# 10_DDR3_RAM.net
KiCad netlist of a schematic drawn in Altium Designer
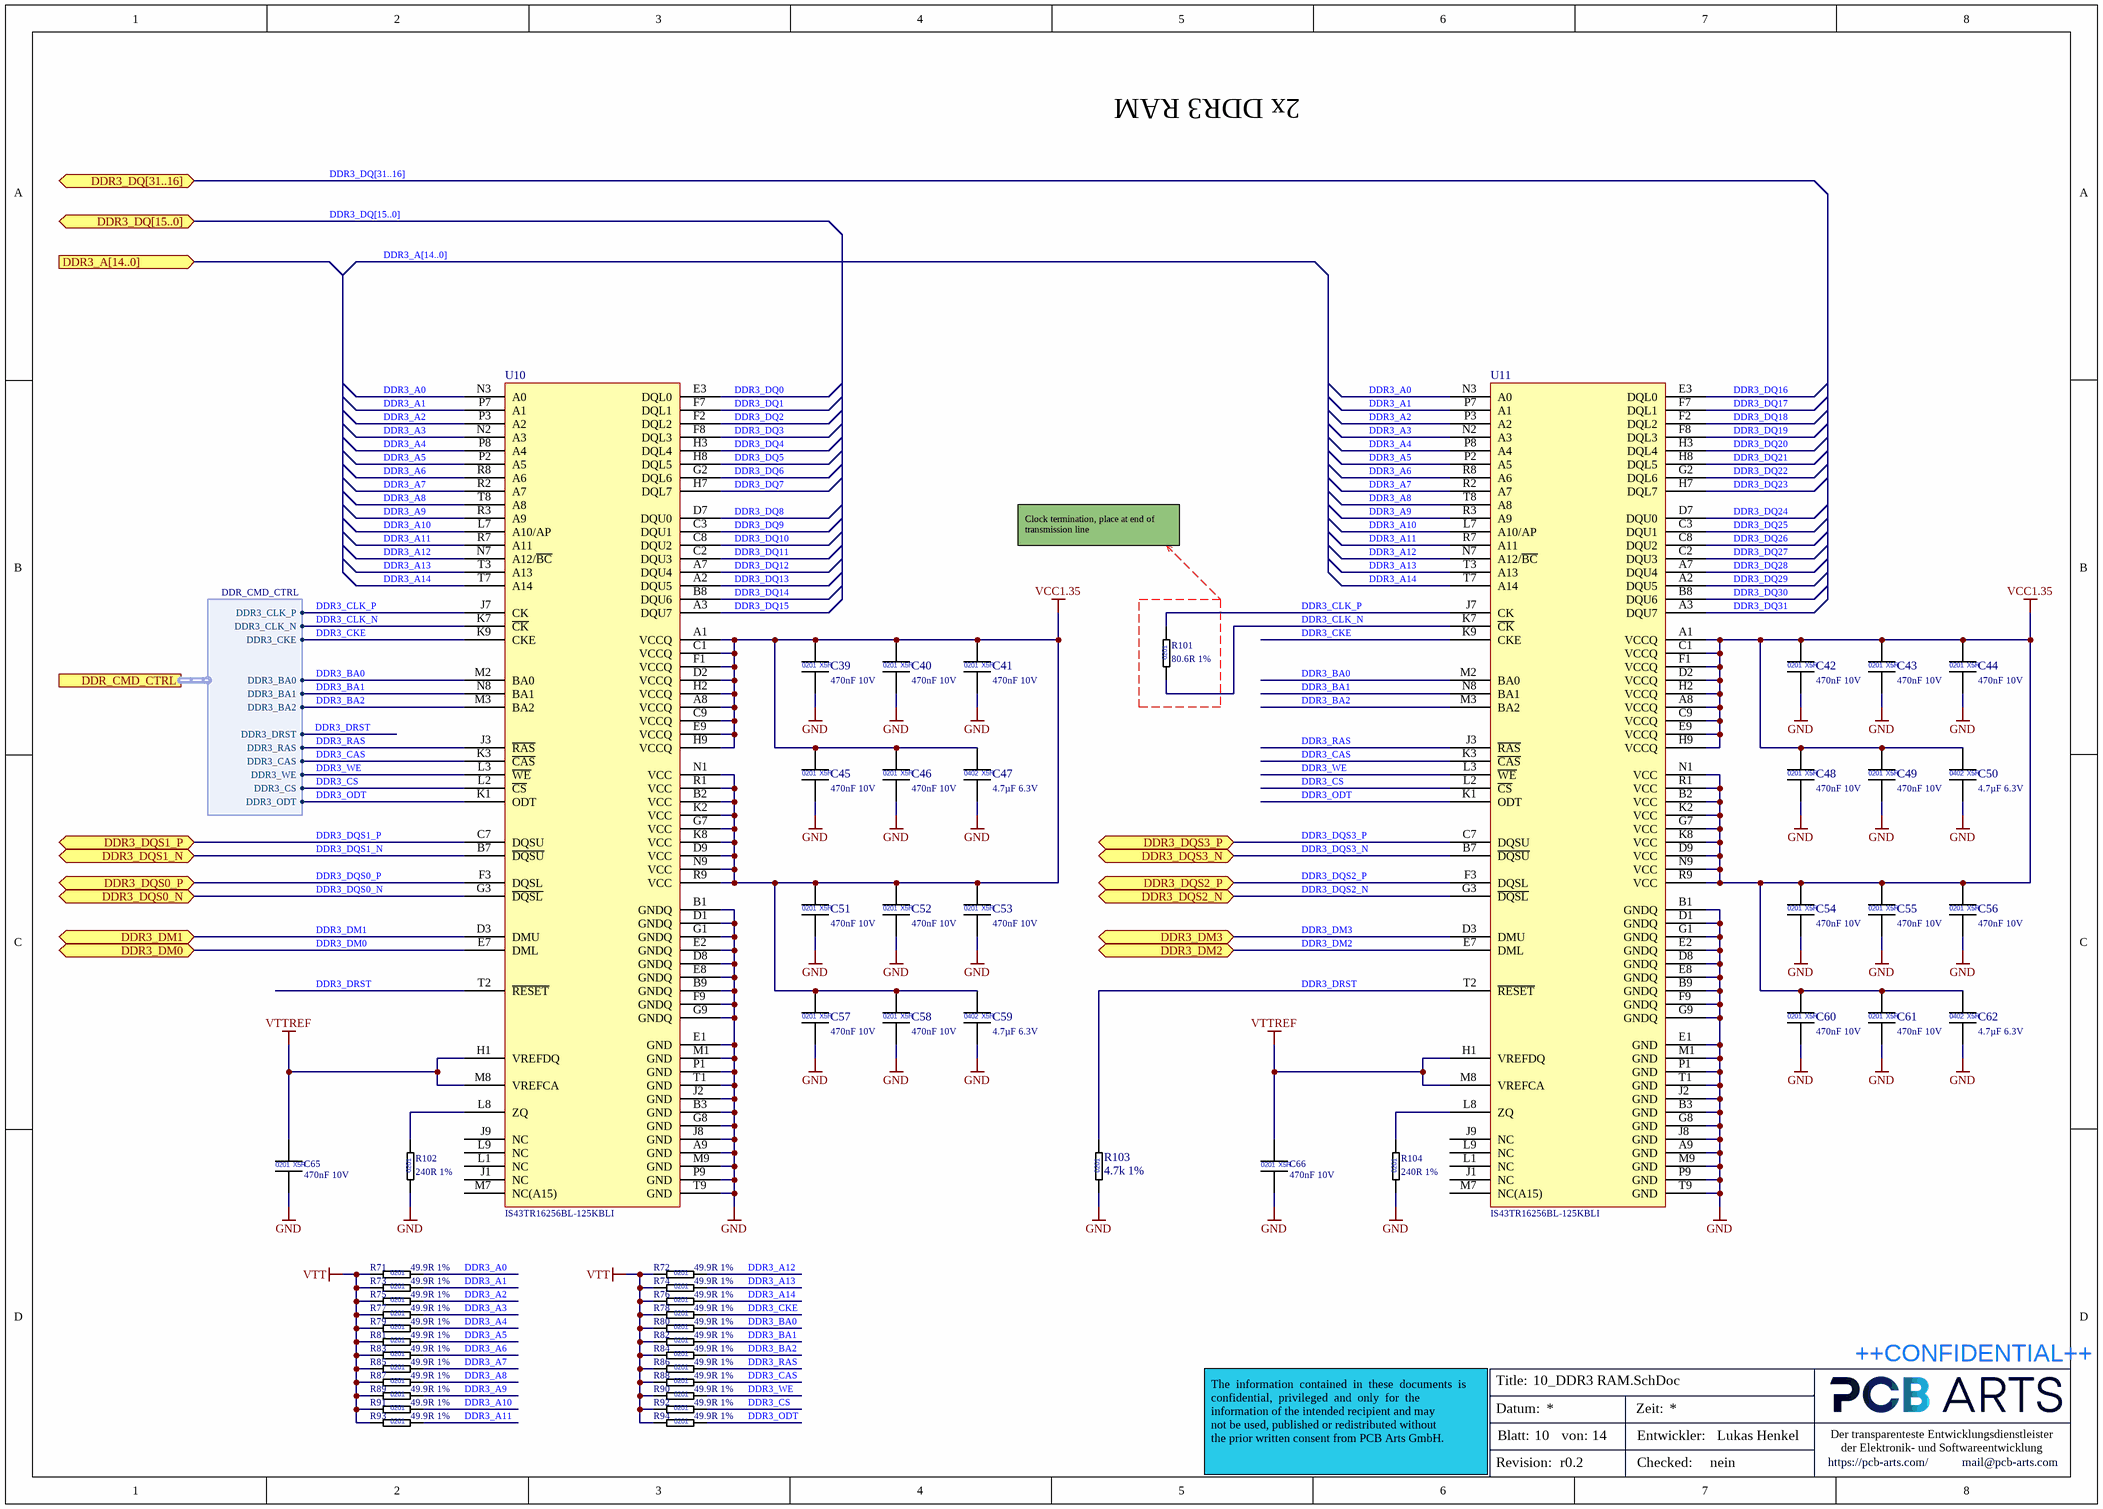
[diagram p0: 10_DDR3 RAM.SchDoc]

(export (version "E")
  (design (tool "Eeschema 10.0.6"))
  (components
    (comp (ref "C39")
      (value "470nF 10V")
      (footprint "Zynq-Feather-HD:CAPC0603X03L")
      (description "Multilayer Ceramic Capacitors MLCC - SMD/SMT 0201 10VDC")
      (libsource (lib "Zynq-Feather-HD") (part "CAP_0201_470nF_10V"))
    )
    (comp (ref "C40")
      (value "470nF 10V")
      (footprint "Zynq-Feather-HD:CAPC0603X03L")
      (description "Multilayer Ceramic Capacitors MLCC - SMD/SMT 0201 10VDC")
      (libsource (lib "Zynq-Feather-HD") (part "CAP_0201_470nF_10V"))
    )
    (comp (ref "C41")
      (value "470nF 10V")
      (footprint "Zynq-Feather-HD:CAPC0603X03L")
      (description "Multilayer Ceramic Capacitors MLCC - SMD/SMT 0201 10VDC")
      (libsource (lib "Zynq-Feather-HD") (part "CAP_0201_470nF_10V"))
    )
    (comp (ref "C42")
      (value "470nF 10V")
      (footprint "Zynq-Feather-HD:CAPC0603X03L")
      (description "Multilayer Ceramic Capacitors MLCC - SMD/SMT 0201 10VDC")
      (libsource (lib "Zynq-Feather-HD") (part "CAP_0201_470nF_10V"))
    )
    (comp (ref "C43")
      (value "470nF 10V")
      (footprint "Zynq-Feather-HD:CAPC0603X03L")
      (description "Multilayer Ceramic Capacitors MLCC - SMD/SMT 0201 10VDC")
      (libsource (lib "Zynq-Feather-HD") (part "CAP_0201_470nF_10V"))
    )
    (comp (ref "C44")
      (value "470nF 10V")
      (footprint "Zynq-Feather-HD:CAPC0603X03L")
      (description "Multilayer Ceramic Capacitors MLCC - SMD/SMT 0201 10VDC")
      (libsource (lib "Zynq-Feather-HD") (part "CAP_0201_470nF_10V"))
    )
    (comp (ref "C45")
      (value "470nF 10V")
      (footprint "Zynq-Feather-HD:CAPC0603X03L")
      (description "Multilayer Ceramic Capacitors MLCC - SMD/SMT 0201 10VDC")
      (libsource (lib "Zynq-Feather-HD") (part "CAP_0201_470nF_10V"))
    )
    (comp (ref "C46")
      (value "470nF 10V")
      (footprint "Zynq-Feather-HD:CAPC0603X03L")
      (description "Multilayer Ceramic Capacitors MLCC - SMD/SMT 0201 10VDC")
      (libsource (lib "Zynq-Feather-HD") (part "CAP_0201_470nF_10V"))
    )
    (comp (ref "C47")
      (value "4.7µF 6.3V")
      (footprint "Zynq-Feather-HD:CAPC1005X06L")
      (description "Multilayer Ceramic Capacitors MLCC - SMD/SMT 0402 6.3VDC")
      (libsource (lib "Zynq-Feather-HD") (part "CAP_0402_4.7µ_6.3V"))
    )
    (comp (ref "C48")
      (value "470nF 10V")
      (footprint "Zynq-Feather-HD:CAPC0603X03L")
      (description "Multilayer Ceramic Capacitors MLCC - SMD/SMT 0201 10VDC")
      (libsource (lib "Zynq-Feather-HD") (part "CAP_0201_470nF_10V"))
    )
    (comp (ref "C49")
      (value "470nF 10V")
      (footprint "Zynq-Feather-HD:CAPC0603X03L")
      (description "Multilayer Ceramic Capacitors MLCC - SMD/SMT 0201 10VDC")
      (libsource (lib "Zynq-Feather-HD") (part "CAP_0201_470nF_10V"))
    )
    (comp (ref "C50")
      (value "4.7µF 6.3V")
      (footprint "Zynq-Feather-HD:CAPC1005X06L")
      (description "Multilayer Ceramic Capacitors MLCC - SMD/SMT 0402 6.3VDC")
      (libsource (lib "Zynq-Feather-HD") (part "CAP_0402_4.7µ_6.3V"))
    )
    (comp (ref "C51")
      (value "470nF 10V")
      (footprint "Zynq-Feather-HD:CAPC0603X03L")
      (description "Multilayer Ceramic Capacitors MLCC - SMD/SMT 0201 10VDC")
      (libsource (lib "Zynq-Feather-HD") (part "CAP_0201_470nF_10V"))
    )
    (comp (ref "C52")
      (value "470nF 10V")
      (footprint "Zynq-Feather-HD:CAPC0603X03L")
      (description "Multilayer Ceramic Capacitors MLCC - SMD/SMT 0201 10VDC")
      (libsource (lib "Zynq-Feather-HD") (part "CAP_0201_470nF_10V"))
    )
    (comp (ref "C53")
      (value "470nF 10V")
      (footprint "Zynq-Feather-HD:CAPC0603X03L")
      (description "Multilayer Ceramic Capacitors MLCC - SMD/SMT 0201 10VDC")
      (libsource (lib "Zynq-Feather-HD") (part "CAP_0201_470nF_10V"))
    )
    (comp (ref "C54")
      (value "470nF 10V")
      (footprint "Zynq-Feather-HD:CAPC0603X03L")
      (description "Multilayer Ceramic Capacitors MLCC - SMD/SMT 0201 10VDC")
      (libsource (lib "Zynq-Feather-HD") (part "CAP_0201_470nF_10V"))
    )
    (comp (ref "C55")
      (value "470nF 10V")
      (footprint "Zynq-Feather-HD:CAPC0603X03L")
      (description "Multilayer Ceramic Capacitors MLCC - SMD/SMT 0201 10VDC")
      (libsource (lib "Zynq-Feather-HD") (part "CAP_0201_470nF_10V"))
    )
    (comp (ref "C56")
      (value "470nF 10V")
      (footprint "Zynq-Feather-HD:CAPC0603X03L")
      (description "Multilayer Ceramic Capacitors MLCC - SMD/SMT 0201 10VDC")
      (libsource (lib "Zynq-Feather-HD") (part "CAP_0201_470nF_10V"))
    )
    (comp (ref "C57")
      (value "470nF 10V")
      (footprint "Zynq-Feather-HD:CAPC0603X03L")
      (description "Multilayer Ceramic Capacitors MLCC - SMD/SMT 0201 10VDC")
      (libsource (lib "Zynq-Feather-HD") (part "CAP_0201_470nF_10V"))
    )
    (comp (ref "C58")
      (value "470nF 10V")
      (footprint "Zynq-Feather-HD:CAPC0603X03L")
      (description "Multilayer Ceramic Capacitors MLCC - SMD/SMT 0201 10VDC")
      (libsource (lib "Zynq-Feather-HD") (part "CAP_0201_470nF_10V"))
    )
    (comp (ref "C59")
      (value "4.7µF 6.3V")
      (footprint "Zynq-Feather-HD:CAPC1005X06L")
      (description "Multilayer Ceramic Capacitors MLCC - SMD/SMT 0402 6.3VDC")
      (libsource (lib "Zynq-Feather-HD") (part "CAP_0402_4.7µ_6.3V"))
    )
    (comp (ref "C60")
      (value "470nF 10V")
      (footprint "Zynq-Feather-HD:CAPC0603X03L")
      (description "Multilayer Ceramic Capacitors MLCC - SMD/SMT 0201 10VDC")
      (libsource (lib "Zynq-Feather-HD") (part "CAP_0201_470nF_10V"))
    )
    (comp (ref "C61")
      (value "470nF 10V")
      (footprint "Zynq-Feather-HD:CAPC0603X03L")
      (description "Multilayer Ceramic Capacitors MLCC - SMD/SMT 0201 10VDC")
      (libsource (lib "Zynq-Feather-HD") (part "CAP_0201_470nF_10V"))
    )
    (comp (ref "C62")
      (value "4.7µF 6.3V")
      (footprint "Zynq-Feather-HD:CAPC1005X06L")
      (description "Multilayer Ceramic Capacitors MLCC - SMD/SMT 0402 6.3VDC")
      (libsource (lib "Zynq-Feather-HD") (part "CAP_0402_4.7µ_6.3V"))
    )
    (comp (ref "C65")
      (value "470nF 10V")
      (footprint "Zynq-Feather-HD:CAPC0603X03L")
      (description "Multilayer Ceramic Capacitors MLCC - SMD/SMT 0201 10VDC")
      (libsource (lib "Zynq-Feather-HD") (part "CAP_0201_470nF_10V"))
    )
    (comp (ref "C66")
      (value "470nF 10V")
      (footprint "Zynq-Feather-HD:CAPC0603X03L")
      (description "Multilayer Ceramic Capacitors MLCC - SMD/SMT 0201 10VDC")
      (libsource (lib "Zynq-Feather-HD") (part "CAP_0201_470nF_10V"))
    )
    (comp (ref "R71")
      (value "49.9R 1%")
      (footprint "Zynq-Feather-HD:RESC0603X03L")
      (description "Thick Film Resistors - SMD 49.9R OHM 1%")
      (libsource (lib "Zynq-Feather-HD") (part "RES_0201_49.9R_1%"))
    )
    (comp (ref "R72")
      (value "49.9R 1%")
      (footprint "Zynq-Feather-HD:RESC0603X03L")
      (description "Thick Film Resistors - SMD 49.9R OHM 1%")
      (libsource (lib "Zynq-Feather-HD") (part "RES_0201_49.9R_1%"))
    )
    (comp (ref "R73")
      (value "49.9R 1%")
      (footprint "Zynq-Feather-HD:RESC0603X03L")
      (description "Thick Film Resistors - SMD 49.9R OHM 1%")
      (libsource (lib "Zynq-Feather-HD") (part "RES_0201_49.9R_1%"))
    )
    (comp (ref "R74")
      (value "49.9R 1%")
      (footprint "Zynq-Feather-HD:RESC0603X03L")
      (description "Thick Film Resistors - SMD 49.9R OHM 1%")
      (libsource (lib "Zynq-Feather-HD") (part "RES_0201_49.9R_1%"))
    )
    (comp (ref "R75")
      (value "49.9R 1%")
      (footprint "Zynq-Feather-HD:RESC0603X03L")
      (description "Thick Film Resistors - SMD 49.9R OHM 1%")
      (libsource (lib "Zynq-Feather-HD") (part "RES_0201_49.9R_1%"))
    )
    (comp (ref "R76")
      (value "49.9R 1%")
      (footprint "Zynq-Feather-HD:RESC0603X03L")
      (description "Thick Film Resistors - SMD 49.9R OHM 1%")
      (libsource (lib "Zynq-Feather-HD") (part "RES_0201_49.9R_1%"))
    )
    (comp (ref "R77")
      (value "49.9R 1%")
      (footprint "Zynq-Feather-HD:RESC0603X03L")
      (description "Thick Film Resistors - SMD 49.9R OHM 1%")
      (libsource (lib "Zynq-Feather-HD") (part "RES_0201_49.9R_1%"))
    )
    (comp (ref "R78")
      (value "49.9R 1%")
      (footprint "Zynq-Feather-HD:RESC0603X03L")
      (description "Thick Film Resistors - SMD 49.9R OHM 1%")
      (libsource (lib "Zynq-Feather-HD") (part "RES_0201_49.9R_1%"))
    )
    (comp (ref "R79")
      (value "49.9R 1%")
      (footprint "Zynq-Feather-HD:RESC0603X03L")
      (description "Thick Film Resistors - SMD 49.9R OHM 1%")
      (libsource (lib "Zynq-Feather-HD") (part "RES_0201_49.9R_1%"))
    )
    (comp (ref "R80")
      (value "49.9R 1%")
      (footprint "Zynq-Feather-HD:RESC0603X03L")
      (description "Thick Film Resistors - SMD 49.9R OHM 1%")
      (libsource (lib "Zynq-Feather-HD") (part "RES_0201_49.9R_1%"))
    )
    (comp (ref "R81")
      (value "49.9R 1%")
      (footprint "Zynq-Feather-HD:RESC0603X03L")
      (description "Thick Film Resistors - SMD 49.9R OHM 1%")
      (libsource (lib "Zynq-Feather-HD") (part "RES_0201_49.9R_1%"))
    )
    (comp (ref "R82")
      (value "49.9R 1%")
      (footprint "Zynq-Feather-HD:RESC0603X03L")
      (description "Thick Film Resistors - SMD 49.9R OHM 1%")
      (libsource (lib "Zynq-Feather-HD") (part "RES_0201_49.9R_1%"))
    )
    (comp (ref "R83")
      (value "49.9R 1%")
      (footprint "Zynq-Feather-HD:RESC0603X03L")
      (description "Thick Film Resistors - SMD 49.9R OHM 1%")
      (libsource (lib "Zynq-Feather-HD") (part "RES_0201_49.9R_1%"))
    )
    (comp (ref "R84")
      (value "49.9R 1%")
      (footprint "Zynq-Feather-HD:RESC0603X03L")
      (description "Thick Film Resistors - SMD 49.9R OHM 1%")
      (libsource (lib "Zynq-Feather-HD") (part "RES_0201_49.9R_1%"))
    )
    (comp (ref "R85")
      (value "49.9R 1%")
      (footprint "Zynq-Feather-HD:RESC0603X03L")
      (description "Thick Film Resistors - SMD 49.9R OHM 1%")
      (libsource (lib "Zynq-Feather-HD") (part "RES_0201_49.9R_1%"))
    )
    (comp (ref "R86")
      (value "49.9R 1%")
      (footprint "Zynq-Feather-HD:RESC0603X03L")
      (description "Thick Film Resistors - SMD 49.9R OHM 1%")
      (libsource (lib "Zynq-Feather-HD") (part "RES_0201_49.9R_1%"))
    )
    (comp (ref "R87")
      (value "49.9R 1%")
      (footprint "Zynq-Feather-HD:RESC0603X03L")
      (description "Thick Film Resistors - SMD 49.9R OHM 1%")
      (libsource (lib "Zynq-Feather-HD") (part "RES_0201_49.9R_1%"))
    )
    (comp (ref "R88")
      (value "49.9R 1%")
      (footprint "Zynq-Feather-HD:RESC0603X03L")
      (description "Thick Film Resistors - SMD 49.9R OHM 1%")
      (libsource (lib "Zynq-Feather-HD") (part "RES_0201_49.9R_1%"))
    )
    (comp (ref "R89")
      (value "49.9R 1%")
      (footprint "Zynq-Feather-HD:RESC0603X03L")
      (description "Thick Film Resistors - SMD 49.9R OHM 1%")
      (libsource (lib "Zynq-Feather-HD") (part "RES_0201_49.9R_1%"))
    )
    (comp (ref "R90")
      (value "49.9R 1%")
      (footprint "Zynq-Feather-HD:RESC0603X03L")
      (description "Thick Film Resistors - SMD 49.9R OHM 1%")
      (libsource (lib "Zynq-Feather-HD") (part "RES_0201_49.9R_1%"))
    )
    (comp (ref "R91")
      (value "49.9R 1%")
      (footprint "Zynq-Feather-HD:RESC0603X03L")
      (description "Thick Film Resistors - SMD 49.9R OHM 1%")
      (libsource (lib "Zynq-Feather-HD") (part "RES_0201_49.9R_1%"))
    )
    (comp (ref "R92")
      (value "49.9R 1%")
      (footprint "Zynq-Feather-HD:RESC0603X03L")
      (description "Thick Film Resistors - SMD 49.9R OHM 1%")
      (libsource (lib "Zynq-Feather-HD") (part "RES_0201_49.9R_1%"))
    )
    (comp (ref "R93")
      (value "49.9R 1%")
      (footprint "Zynq-Feather-HD:RESC0603X03L")
      (description "Thick Film Resistors - SMD 49.9R OHM 1%")
      (libsource (lib "Zynq-Feather-HD") (part "RES_0201_49.9R_1%"))
    )
    (comp (ref "R94")
      (value "49.9R 1%")
      (footprint "Zynq-Feather-HD:RESC0603X03L")
      (description "Thick Film Resistors - SMD 49.9R OHM 1%")
      (libsource (lib "Zynq-Feather-HD") (part "RES_0201_49.9R_1%"))
    )
    (comp (ref "R101")
      (value "80.6R 1%")
      (footprint "Zynq-Feather-HD:RESC0603X03L")
      (description "Thick Film Resistors - SMD 80.6R OHM 1%")
      (libsource (lib "Zynq-Feather-HD") (part "RES_0201_80.6R_1%"))
    )
    (comp (ref "R102")
      (value "240R 1%")
      (footprint "Zynq-Feather-HD:RESC0603X03L")
      (description "Thick Film Resistors - SMD 240 OHM 1%")
      (libsource (lib "Zynq-Feather-HD") (part "RES_0201_240R_1%"))
    )
    (comp (ref "R103")
      (value "4.7k 1%")
      (footprint "Zynq-Feather-HD:RESC0603X03L")
      (description "Thick Film Resistors - SMD 4.7K OHM 1%")
      (libsource (lib "Zynq-Feather-HD") (part "RES_0201_4.7k_1%"))
    )
    (comp (ref "R104")
      (value "240R 1%")
      (footprint "Zynq-Feather-HD:RESC0603X03L")
      (description "Thick Film Resistors - SMD 240 OHM 1%")
      (libsource (lib "Zynq-Feather-HD") (part "RES_0201_240R_1%"))
    )
    (comp (ref "U10")
      (value "IS43TR16256BL-125KBLI")
      (footprint "Zynq-Feather-HD:BGA96C80P9X16_900X1300X120")
      (description "DRAM 4G, 1.35V, DDR3L, 256Mx16, 1600MT/s @ 11-11-11, 96 ball BGA (9mm x13mm) RoHS, IT")
      (libsource (lib "Zynq-Feather-HD") (part "IS43TR16256BL-125KBLI_DRAM 4G, 1.35V, DDR3L, 256Mx16"))
    )
    (comp (ref "U11")
      (value "IS43TR16256BL-125KBLI")
      (footprint "Zynq-Feather-HD:BGA96C80P9X16_900X1300X120")
      (description "DRAM 4G, 1.35V, DDR3L, 256Mx16, 1600MT/s @ 11-11-11, 96 ball BGA (9mm x13mm) RoHS, IT")
      (libsource (lib "Zynq-Feather-HD") (part "IS43TR16256BL-125KBLI_DRAM 4G, 1.35V, DDR3L, 256Mx16"))
    )
  )
  (nets
    (net (code "2") (name "/DDR3_A0") (class "Default")
      (node (ref "R71") (pin "2") (pinfunction "2_2") (pintype "passive"))
      (node (ref "U10") (pin "N3") (pinfunction "A0_N3") (pintype "passive"))
      (node (ref "U11") (pin "N3") (pinfunction "A0_N3") (pintype "passive"))
    )
    (net (code "3") (name "/DDR3_A1") (class "Default")
      (node (ref "R73") (pin "2") (pinfunction "2_2") (pintype "passive"))
      (node (ref "U10") (pin "P7") (pinfunction "A1_P7") (pintype "passive"))
      (node (ref "U11") (pin "P7") (pinfunction "A1_P7") (pintype "passive"))
    )
    (net (code "4") (name "/DDR3_A2") (class "Default")
      (node (ref "R75") (pin "2") (pinfunction "2_2") (pintype "passive"))
      (node (ref "U10") (pin "P3") (pinfunction "A2_P3") (pintype "passive"))
      (node (ref "U11") (pin "P3") (pinfunction "A2_P3") (pintype "passive"))
    )
    (net (code "5") (name "/DDR3_A3") (class "Default")
      (node (ref "R77") (pin "2") (pinfunction "2_2") (pintype "passive"))
      (node (ref "U10") (pin "N2") (pinfunction "A3_N2") (pintype "passive"))
      (node (ref "U11") (pin "N2") (pinfunction "A3_N2") (pintype "passive"))
    )
    (net (code "6") (name "/DDR3_A4") (class "Default")
      (node (ref "R79") (pin "2") (pinfunction "2_2") (pintype "passive"))
      (node (ref "U10") (pin "P8") (pinfunction "A4_P8") (pintype "passive"))
      (node (ref "U11") (pin "P8") (pinfunction "A4_P8") (pintype "passive"))
    )
    (net (code "7") (name "/DDR3_A5") (class "Default")
      (node (ref "R81") (pin "2") (pinfunction "2_2") (pintype "passive"))
      (node (ref "U10") (pin "P2") (pinfunction "A5_P2") (pintype "passive"))
      (node (ref "U11") (pin "P2") (pinfunction "A5_P2") (pintype "passive"))
    )
    (net (code "8") (name "/DDR3_A6") (class "Default")
      (node (ref "R83") (pin "2") (pinfunction "2_2") (pintype "passive"))
      (node (ref "U10") (pin "R8") (pinfunction "A6_R8") (pintype "passive"))
      (node (ref "U11") (pin "R8") (pinfunction "A6_R8") (pintype "passive"))
    )
    (net (code "9") (name "/DDR3_A7") (class "Default")
      (node (ref "R85") (pin "2") (pinfunction "2_2") (pintype "passive"))
      (node (ref "U10") (pin "R2") (pinfunction "A7_R2") (pintype "passive"))
      (node (ref "U11") (pin "R2") (pinfunction "A7_R2") (pintype "passive"))
    )
    (net (code "10") (name "/DDR3_A8") (class "Default")
      (node (ref "R87") (pin "2") (pinfunction "2_2") (pintype "passive"))
      (node (ref "U10") (pin "T8") (pinfunction "A8_T8") (pintype "passive"))
      (node (ref "U11") (pin "T8") (pinfunction "A8_T8") (pintype "passive"))
    )
    (net (code "11") (name "/DDR3_A9") (class "Default")
      (node (ref "R89") (pin "2") (pinfunction "2_2") (pintype "passive"))
      (node (ref "U10") (pin "R3") (pinfunction "A9_R3") (pintype "passive"))
      (node (ref "U11") (pin "R3") (pinfunction "A9_R3") (pintype "passive"))
    )
    (net (code "12") (name "/DDR3_A10") (class "Default")
      (node (ref "R91") (pin "2") (pinfunction "2_2") (pintype "passive"))
      (node (ref "U10") (pin "L7") (pinfunction "A10/AP_L7") (pintype "passive"))
      (node (ref "U11") (pin "L7") (pinfunction "A10/AP_L7") (pintype "passive"))
    )
    (net (code "13") (name "/DDR3_A11") (class "Default")
      (node (ref "R93") (pin "2") (pinfunction "2_2") (pintype "passive"))
      (node (ref "U10") (pin "R7") (pinfunction "A11_R7") (pintype "passive"))
      (node (ref "U11") (pin "R7") (pinfunction "A11_R7") (pintype "passive"))
    )
    (net (code "14") (name "/DDR3_A12") (class "Default")
      (node (ref "R72") (pin "2") (pinfunction "2_2") (pintype "passive"))
      (node (ref "U10") (pin "N7") (pinfunction "A12/~{BC}_N7") (pintype "passive"))
      (node (ref "U11") (pin "N7") (pinfunction "A12/~{BC}_N7") (pintype "passive"))
    )
    (net (code "15") (name "/DDR3_A13") (class "Default")
      (node (ref "R74") (pin "2") (pinfunction "2_2") (pintype "passive"))
      (node (ref "U10") (pin "T3") (pinfunction "A13_T3") (pintype "passive"))
      (node (ref "U11") (pin "T3") (pinfunction "A13_T3") (pintype "passive"))
    )
    (net (code "16") (name "/DDR3_A14") (class "Default")
      (node (ref "R76") (pin "2") (pinfunction "2_2") (pintype "passive"))
      (node (ref "U10") (pin "T7") (pinfunction "A14_T7") (pintype "passive"))
      (node (ref "U11") (pin "T7") (pinfunction "A14_T7") (pintype "passive"))
    )
    (net (code "18") (name "/DDR3_BA0") (class "Default")
      (node (ref "R80") (pin "2") (pinfunction "2_2") (pintype "passive"))
      (node (ref "U10") (pin "M2") (pinfunction "BA0_M2") (pintype "passive"))
      (node (ref "U11") (pin "M2") (pinfunction "BA0_M2") (pintype "passive"))
    )
    (net (code "19") (name "/DDR3_BA1") (class "Default")
      (node (ref "R82") (pin "2") (pinfunction "2_2") (pintype "passive"))
      (node (ref "U10") (pin "N8") (pinfunction "BA1_N8") (pintype "passive"))
      (node (ref "U11") (pin "N8") (pinfunction "BA1_N8") (pintype "passive"))
    )
    (net (code "20") (name "/DDR3_BA2") (class "Default")
      (node (ref "R84") (pin "2") (pinfunction "2_2") (pintype "passive"))
      (node (ref "U10") (pin "M3") (pinfunction "BA2_M3") (pintype "passive"))
      (node (ref "U11") (pin "M3") (pinfunction "BA2_M3") (pintype "passive"))
    )
    (net (code "21") (name "/DDR3_CAS") (class "Default")
      (node (ref "R88") (pin "2") (pinfunction "2_2") (pintype "passive"))
      (node (ref "U10") (pin "K3") (pinfunction "~{CAS}_K3") (pintype "passive"))
      (node (ref "U11") (pin "K3") (pinfunction "~{CAS}_K3") (pintype "passive"))
    )
    (net (code "22") (name "/DDR3_CKE") (class "Default")
      (node (ref "R78") (pin "2") (pinfunction "2_2") (pintype "passive"))
      (node (ref "U10") (pin "K9") (pinfunction "CKE_K9") (pintype "passive"))
      (node (ref "U11") (pin "K9") (pinfunction "CKE_K9") (pintype "passive"))
    )
    (net (code "23") (name "/DDR3_CLK_N") (class "Default")
      (node (ref "R101") (pin "1") (pinfunction "1_1") (pintype "passive"))
      (node (ref "U10") (pin "K7") (pinfunction "~{CK}_K7") (pintype "passive"))
      (node (ref "U11") (pin "K7") (pinfunction "~{CK}_K7") (pintype "passive"))
    )
    (net (code "24") (name "/DDR3_CLK_P") (class "Default")
      (node (ref "R101") (pin "2") (pinfunction "2_2") (pintype "passive"))
      (node (ref "U10") (pin "J7") (pinfunction "CK_J7") (pintype "passive"))
      (node (ref "U11") (pin "J7") (pinfunction "CK_J7") (pintype "passive"))
    )
    (net (code "25") (name "/DDR3_CS") (class "Default")
      (node (ref "R92") (pin "2") (pinfunction "2_2") (pintype "passive"))
      (node (ref "U10") (pin "L2") (pinfunction "~{CS}_L2") (pintype "passive"))
      (node (ref "U11") (pin "L2") (pinfunction "~{CS}_L2") (pintype "passive"))
    )
    (net (code "26") (name "/DDR3_DM0") (class "Default")
      (node (ref "U10") (pin "E7") (pinfunction "DML_E7") (pintype "passive"))
    )
    (net (code "27") (name "/DDR3_DM1") (class "Default")
      (node (ref "U10") (pin "D3") (pinfunction "DMU_D3") (pintype "passive"))
    )
    (net (code "28") (name "/DDR3_DM2") (class "Default")
      (node (ref "U11") (pin "E7") (pinfunction "DML_E7") (pintype "passive"))
    )
    (net (code "29") (name "/DDR3_DM3") (class "Default")
      (node (ref "U11") (pin "D3") (pinfunction "DMU_D3") (pintype "passive"))
    )
    (net (code "30") (name "/DDR3_DQ0") (class "Default")
      (node (ref "U10") (pin "E3") (pinfunction "DQL0_E3") (pintype "passive"))
    )
    (net (code "31") (name "/DDR3_DQ1") (class "Default")
      (node (ref "U10") (pin "F7") (pinfunction "DQL1_F7") (pintype "passive"))
    )
    (net (code "32") (name "/DDR3_DQ2") (class "Default")
      (node (ref "U10") (pin "F2") (pinfunction "DQL2_F2") (pintype "passive"))
    )
    (net (code "33") (name "/DDR3_DQ3") (class "Default")
      (node (ref "U10") (pin "F8") (pinfunction "DQL3_F8") (pintype "passive"))
    )
    (net (code "34") (name "/DDR3_DQ4") (class "Default")
      (node (ref "U10") (pin "H3") (pinfunction "DQL4_H3") (pintype "passive"))
    )
    (net (code "35") (name "/DDR3_DQ5") (class "Default")
      (node (ref "U10") (pin "H8") (pinfunction "DQL5_H8") (pintype "passive"))
    )
    (net (code "36") (name "/DDR3_DQ6") (class "Default")
      (node (ref "U10") (pin "G2") (pinfunction "DQL6_G2") (pintype "passive"))
    )
    (net (code "37") (name "/DDR3_DQ7") (class "Default")
      (node (ref "U10") (pin "H7") (pinfunction "DQL7_H7") (pintype "passive"))
    )
    (net (code "38") (name "/DDR3_DQ8") (class "Default")
      (node (ref "U10") (pin "D7") (pinfunction "DQU0_D7") (pintype "passive"))
    )
    (net (code "39") (name "/DDR3_DQ9") (class "Default")
      (node (ref "U10") (pin "C3") (pinfunction "DQU1_C3") (pintype "passive"))
    )
    (net (code "40") (name "/DDR3_DQ10") (class "Default")
      (node (ref "U10") (pin "C8") (pinfunction "DQU2_C8") (pintype "passive"))
    )
    (net (code "41") (name "/DDR3_DQ11") (class "Default")
      (node (ref "U10") (pin "C2") (pinfunction "DQU3_C2") (pintype "passive"))
    )
    (net (code "42") (name "/DDR3_DQ12") (class "Default")
      (node (ref "U10") (pin "A7") (pinfunction "DQU4_A7") (pintype "passive"))
    )
    (net (code "43") (name "/DDR3_DQ13") (class "Default")
      (node (ref "U10") (pin "A2") (pinfunction "DQU5_A2") (pintype "passive"))
    )
    (net (code "44") (name "/DDR3_DQ14") (class "Default")
      (node (ref "U10") (pin "B8") (pinfunction "DQU6_B8") (pintype "passive"))
    )
    (net (code "45") (name "/DDR3_DQ15") (class "Default")
      (node (ref "U10") (pin "A3") (pinfunction "DQU7_A3") (pintype "passive"))
    )
    (net (code "46") (name "/DDR3_DQ16") (class "Default")
      (node (ref "U11") (pin "E3") (pinfunction "DQL0_E3") (pintype "passive"))
    )
    (net (code "47") (name "/DDR3_DQ17") (class "Default")
      (node (ref "U11") (pin "F7") (pinfunction "DQL1_F7") (pintype "passive"))
    )
    (net (code "48") (name "/DDR3_DQ18") (class "Default")
      (node (ref "U11") (pin "F2") (pinfunction "DQL2_F2") (pintype "passive"))
    )
    (net (code "49") (name "/DDR3_DQ19") (class "Default")
      (node (ref "U11") (pin "F8") (pinfunction "DQL3_F8") (pintype "passive"))
    )
    (net (code "50") (name "/DDR3_DQ20") (class "Default")
      (node (ref "U11") (pin "H3") (pinfunction "DQL4_H3") (pintype "passive"))
    )
    (net (code "51") (name "/DDR3_DQ21") (class "Default")
      (node (ref "U11") (pin "H8") (pinfunction "DQL5_H8") (pintype "passive"))
    )
    (net (code "52") (name "/DDR3_DQ22") (class "Default")
      (node (ref "U11") (pin "G2") (pinfunction "DQL6_G2") (pintype "passive"))
    )
    (net (code "53") (name "/DDR3_DQ23") (class "Default")
      (node (ref "U11") (pin "H7") (pinfunction "DQL7_H7") (pintype "passive"))
    )
    (net (code "54") (name "/DDR3_DQ24") (class "Default")
      (node (ref "U11") (pin "D7") (pinfunction "DQU0_D7") (pintype "passive"))
    )
    (net (code "55") (name "/DDR3_DQ25") (class "Default")
      (node (ref "U11") (pin "C3") (pinfunction "DQU1_C3") (pintype "passive"))
    )
    (net (code "56") (name "/DDR3_DQ26") (class "Default")
      (node (ref "U11") (pin "C8") (pinfunction "DQU2_C8") (pintype "passive"))
    )
    (net (code "57") (name "/DDR3_DQ27") (class "Default")
      (node (ref "U11") (pin "C2") (pinfunction "DQU3_C2") (pintype "passive"))
    )
    (net (code "58") (name "/DDR3_DQ28") (class "Default")
      (node (ref "U11") (pin "A7") (pinfunction "DQU4_A7") (pintype "passive"))
    )
    (net (code "59") (name "/DDR3_DQ29") (class "Default")
      (node (ref "U11") (pin "A2") (pinfunction "DQU5_A2") (pintype "passive"))
    )
    (net (code "60") (name "/DDR3_DQ30") (class "Default")
      (node (ref "U11") (pin "B8") (pinfunction "DQU6_B8") (pintype "passive"))
    )
    (net (code "61") (name "/DDR3_DQ31") (class "Default")
      (node (ref "U11") (pin "A3") (pinfunction "DQU7_A3") (pintype "passive"))
    )
    (net (code "62") (name "/DDR3_DQS0_N") (class "Default")
      (node (ref "U10") (pin "G3") (pinfunction "~{DQSL}_G3") (pintype "passive"))
    )
    (net (code "63") (name "/DDR3_DQS0_P") (class "Default")
      (node (ref "U10") (pin "F3") (pinfunction "DQSL_F3") (pintype "passive"))
    )
    (net (code "64") (name "/DDR3_DQS1_N") (class "Default")
      (node (ref "U10") (pin "B7") (pinfunction "~{DQSU}_B7") (pintype "passive"))
    )
    (net (code "65") (name "/DDR3_DQS1_P") (class "Default")
      (node (ref "U10") (pin "C7") (pinfunction "DQSU_C7") (pintype "passive"))
    )
    (net (code "66") (name "/DDR3_DQS2_N") (class "Default")
      (node (ref "U11") (pin "G3") (pinfunction "~{DQSL}_G3") (pintype "passive"))
    )
    (net (code "67") (name "/DDR3_DQS2_P") (class "Default")
      (node (ref "U11") (pin "F3") (pinfunction "DQSL_F3") (pintype "passive"))
    )
    (net (code "68") (name "/DDR3_DQS3_N") (class "Default")
      (node (ref "U11") (pin "B7") (pinfunction "~{DQSU}_B7") (pintype "passive"))
    )
    (net (code "69") (name "/DDR3_DQS3_P") (class "Default")
      (node (ref "U11") (pin "C7") (pinfunction "DQSU_C7") (pintype "passive"))
    )
    (net (code "72") (name "/DDR3_DRST") (class "Default")
      (node (ref "R103") (pin "2") (pinfunction "2_2") (pintype "passive"))
      (node (ref "U10") (pin "T2") (pinfunction "~{RESET}_T2") (pintype "passive"))
      (node (ref "U11") (pin "T2") (pinfunction "~{RESET}_T2") (pintype "passive"))
    )
    (net (code "73") (name "/DDR3_ODT") (class "Default")
      (node (ref "R94") (pin "2") (pinfunction "2_2") (pintype "passive"))
      (node (ref "U10") (pin "K1") (pinfunction "ODT_K1") (pintype "passive"))
      (node (ref "U11") (pin "K1") (pinfunction "ODT_K1") (pintype "passive"))
    )
    (net (code "74") (name "/DDR3_RAS") (class "Default")
      (node (ref "R86") (pin "2") (pinfunction "2_2") (pintype "passive"))
      (node (ref "U10") (pin "J3") (pinfunction "~{RAS}_J3") (pintype "passive"))
      (node (ref "U11") (pin "J3") (pinfunction "~{RAS}_J3") (pintype "passive"))
    )
    (net (code "75") (name "/DDR3_WE") (class "Default")
      (node (ref "R90") (pin "2") (pinfunction "2_2") (pintype "passive"))
      (node (ref "U10") (pin "L3") (pinfunction "~{WE}_L3") (pintype "passive"))
      (node (ref "U11") (pin "L3") (pinfunction "~{WE}_L3") (pintype "passive"))
    )
    (net (code "77") (name "GND") (class "Default")
      (node (ref "C39") (pin "2") (pinfunction "2_2") (pintype "passive"))
      (node (ref "C40") (pin "2") (pinfunction "2_2") (pintype "passive"))
      (node (ref "C41") (pin "2") (pinfunction "2_2") (pintype "passive"))
      (node (ref "C42") (pin "2") (pinfunction "2_2") (pintype "passive"))
      (node (ref "C43") (pin "2") (pinfunction "2_2") (pintype "passive"))
      (node (ref "C44") (pin "2") (pinfunction "2_2") (pintype "passive"))
      (node (ref "C45") (pin "2") (pinfunction "2_2") (pintype "passive"))
      (node (ref "C46") (pin "2") (pinfunction "2_2") (pintype "passive"))
      (node (ref "C47") (pin "2") (pinfunction "2_2") (pintype "passive"))
      (node (ref "C48") (pin "2") (pinfunction "2_2") (pintype "passive"))
      (node (ref "C49") (pin "2") (pinfunction "2_2") (pintype "passive"))
      (node (ref "C50") (pin "2") (pinfunction "2_2") (pintype "passive"))
      (node (ref "C51") (pin "2") (pinfunction "2_2") (pintype "passive"))
      (node (ref "C52") (pin "2") (pinfunction "2_2") (pintype "passive"))
      (node (ref "C53") (pin "2") (pinfunction "2_2") (pintype "passive"))
      (node (ref "C54") (pin "2") (pinfunction "2_2") (pintype "passive"))
      (node (ref "C55") (pin "2") (pinfunction "2_2") (pintype "passive"))
      (node (ref "C56") (pin "2") (pinfunction "2_2") (pintype "passive"))
      (node (ref "C57") (pin "2") (pinfunction "2_2") (pintype "passive"))
      (node (ref "C58") (pin "2") (pinfunction "2_2") (pintype "passive"))
      (node (ref "C59") (pin "2") (pinfunction "2_2") (pintype "passive"))
      (node (ref "C60") (pin "2") (pinfunction "2_2") (pintype "passive"))
      (node (ref "C61") (pin "2") (pinfunction "2_2") (pintype "passive"))
      (node (ref "C62") (pin "2") (pinfunction "2_2") (pintype "passive"))
      (node (ref "C65") (pin "2") (pinfunction "2_2") (pintype "passive"))
      (node (ref "C66") (pin "2") (pinfunction "2_2") (pintype "passive"))
      (node (ref "R102") (pin "1") (pinfunction "1_1") (pintype "passive"))
      (node (ref "R103") (pin "1") (pinfunction "1_1") (pintype "passive"))
      (node (ref "R104") (pin "1") (pinfunction "1_1") (pintype "passive"))
      (node (ref "U10") (pin "A9") (pinfunction "GND_A9") (pintype "passive"))
      (node (ref "U10") (pin "B1") (pinfunction "GNDQ_B1") (pintype "passive"))
      (node (ref "U10") (pin "B3") (pinfunction "GND_B3") (pintype "passive"))
      (node (ref "U10") (pin "B9") (pinfunction "GNDQ_B9") (pintype "passive"))
      (node (ref "U10") (pin "D1") (pinfunction "GNDQ_D1") (pintype "passive"))
      (node (ref "U10") (pin "D8") (pinfunction "GNDQ_D8") (pintype "passive"))
      (node (ref "U10") (pin "E1") (pinfunction "GND_E1") (pintype "passive"))
      (node (ref "U10") (pin "E2") (pinfunction "GNDQ_E2") (pintype "passive"))
      (node (ref "U10") (pin "E8") (pinfunction "GNDQ_E8") (pintype "passive"))
      (node (ref "U10") (pin "F9") (pinfunction "GNDQ_F9") (pintype "passive"))
      (node (ref "U10") (pin "G1") (pinfunction "GNDQ_G1") (pintype "passive"))
      (node (ref "U10") (pin "G8") (pinfunction "GND_G8") (pintype "passive"))
      (node (ref "U10") (pin "G9") (pinfunction "GNDQ_G9") (pintype "passive"))
      (node (ref "U10") (pin "J2") (pinfunction "GND_J2") (pintype "passive"))
      (node (ref "U10") (pin "J8") (pinfunction "GND_J8") (pintype "passive"))
      (node (ref "U10") (pin "M1") (pinfunction "GND_M1") (pintype "passive"))
      (node (ref "U10") (pin "M9") (pinfunction "GND_M9") (pintype "passive"))
      (node (ref "U10") (pin "P1") (pinfunction "GND_P1") (pintype "passive"))
      (node (ref "U10") (pin "P9") (pinfunction "GND_P9") (pintype "passive"))
      (node (ref "U10") (pin "T1") (pinfunction "GND_T1") (pintype "passive"))
      (node (ref "U10") (pin "T9") (pinfunction "GND_T9") (pintype "passive"))
      (node (ref "U11") (pin "A9") (pinfunction "GND_A9") (pintype "passive"))
      (node (ref "U11") (pin "B1") (pinfunction "GNDQ_B1") (pintype "passive"))
      (node (ref "U11") (pin "B3") (pinfunction "GND_B3") (pintype "passive"))
      (node (ref "U11") (pin "B9") (pinfunction "GNDQ_B9") (pintype "passive"))
      (node (ref "U11") (pin "D1") (pinfunction "GNDQ_D1") (pintype "passive"))
      (node (ref "U11") (pin "D8") (pinfunction "GNDQ_D8") (pintype "passive"))
      (node (ref "U11") (pin "E1") (pinfunction "GND_E1") (pintype "passive"))
      (node (ref "U11") (pin "E2") (pinfunction "GNDQ_E2") (pintype "passive"))
      (node (ref "U11") (pin "E8") (pinfunction "GNDQ_E8") (pintype "passive"))
      (node (ref "U11") (pin "F9") (pinfunction "GNDQ_F9") (pintype "passive"))
      (node (ref "U11") (pin "G1") (pinfunction "GNDQ_G1") (pintype "passive"))
      (node (ref "U11") (pin "G8") (pinfunction "GND_G8") (pintype "passive"))
      (node (ref "U11") (pin "G9") (pinfunction "GNDQ_G9") (pintype "passive"))
      (node (ref "U11") (pin "J2") (pinfunction "GND_J2") (pintype "passive"))
      (node (ref "U11") (pin "J8") (pinfunction "GND_J8") (pintype "passive"))
      (node (ref "U11") (pin "M1") (pinfunction "GND_M1") (pintype "passive"))
      (node (ref "U11") (pin "M9") (pinfunction "GND_M9") (pintype "passive"))
      (node (ref "U11") (pin "P1") (pinfunction "GND_P1") (pintype "passive"))
      (node (ref "U11") (pin "P9") (pinfunction "GND_P9") (pintype "passive"))
      (node (ref "U11") (pin "T1") (pinfunction "GND_T1") (pintype "passive"))
      (node (ref "U11") (pin "T9") (pinfunction "GND_T9") (pintype "passive"))
    )
    (net (code "78") (name "Net-(U10-ZQ)") (class "Default")
      (node (ref "R102") (pin "2") (pinfunction "2_2") (pintype "passive"))
      (node (ref "U10") (pin "L8") (pinfunction "ZQ_L8") (pintype "passive"))
    )
    (net (code "79") (name "Net-(U11-ZQ)") (class "Default")
      (node (ref "R104") (pin "2") (pinfunction "2_2") (pintype "passive"))
      (node (ref "U11") (pin "L8") (pinfunction "ZQ_L8") (pintype "passive"))
    )
    (net (code "80") (name "VCC1.35") (class "Default")
      (node (ref "C39") (pin "1") (pinfunction "1_1") (pintype "passive"))
      (node (ref "C40") (pin "1") (pinfunction "1_1") (pintype "passive"))
      (node (ref "C41") (pin "1") (pinfunction "1_1") (pintype "passive"))
      (node (ref "C42") (pin "1") (pinfunction "1_1") (pintype "passive"))
      (node (ref "C43") (pin "1") (pinfunction "1_1") (pintype "passive"))
      (node (ref "C44") (pin "1") (pinfunction "1_1") (pintype "passive"))
      (node (ref "C45") (pin "1") (pinfunction "1_1") (pintype "passive"))
      (node (ref "C46") (pin "1") (pinfunction "1_1") (pintype "passive"))
      (node (ref "C47") (pin "1") (pinfunction "1_1") (pintype "passive"))
      (node (ref "C48") (pin "1") (pinfunction "1_1") (pintype "passive"))
      (node (ref "C49") (pin "1") (pinfunction "1_1") (pintype "passive"))
      (node (ref "C50") (pin "1") (pinfunction "1_1") (pintype "passive"))
      (node (ref "C51") (pin "1") (pinfunction "1_1") (pintype "passive"))
      (node (ref "C52") (pin "1") (pinfunction "1_1") (pintype "passive"))
      (node (ref "C53") (pin "1") (pinfunction "1_1") (pintype "passive"))
      (node (ref "C54") (pin "1") (pinfunction "1_1") (pintype "passive"))
      (node (ref "C55") (pin "1") (pinfunction "1_1") (pintype "passive"))
      (node (ref "C56") (pin "1") (pinfunction "1_1") (pintype "passive"))
      (node (ref "C57") (pin "1") (pinfunction "1_1") (pintype "passive"))
      (node (ref "C58") (pin "1") (pinfunction "1_1") (pintype "passive"))
      (node (ref "C59") (pin "1") (pinfunction "1_1") (pintype "passive"))
      (node (ref "C60") (pin "1") (pinfunction "1_1") (pintype "passive"))
      (node (ref "C61") (pin "1") (pinfunction "1_1") (pintype "passive"))
      (node (ref "C62") (pin "1") (pinfunction "1_1") (pintype "passive"))
      (node (ref "U10") (pin "A1") (pinfunction "VCCQ_A1") (pintype "passive"))
      (node (ref "U10") (pin "A8") (pinfunction "VCCQ_A8") (pintype "passive"))
      (node (ref "U10") (pin "B2") (pinfunction "VCC_B2") (pintype "passive"))
      (node (ref "U10") (pin "C1") (pinfunction "VCCQ_C1") (pintype "passive"))
      (node (ref "U10") (pin "C9") (pinfunction "VCCQ_C9") (pintype "passive"))
      (node (ref "U10") (pin "D2") (pinfunction "VCCQ_D2") (pintype "passive"))
      (node (ref "U10") (pin "D9") (pinfunction "VCC_D9") (pintype "passive"))
      (node (ref "U10") (pin "E9") (pinfunction "VCCQ_E9") (pintype "passive"))
      (node (ref "U10") (pin "F1") (pinfunction "VCCQ_F1") (pintype "passive"))
      (node (ref "U10") (pin "G7") (pinfunction "VCC_G7") (pintype "passive"))
      (node (ref "U10") (pin "H2") (pinfunction "VCCQ_H2") (pintype "passive"))
      (node (ref "U10") (pin "H9") (pinfunction "VCCQ_H9") (pintype "passive"))
      (node (ref "U10") (pin "K2") (pinfunction "VCC_K2") (pintype "passive"))
      (node (ref "U10") (pin "K8") (pinfunction "VCC_K8") (pintype "passive"))
      (node (ref "U10") (pin "N1") (pinfunction "VCC_N1") (pintype "passive"))
      (node (ref "U10") (pin "N9") (pinfunction "VCC_N9") (pintype "passive"))
      (node (ref "U10") (pin "R1") (pinfunction "VCC_R1") (pintype "passive"))
      (node (ref "U10") (pin "R9") (pinfunction "VCC_R9") (pintype "passive"))
      (node (ref "U11") (pin "A1") (pinfunction "VCCQ_A1") (pintype "passive"))
      (node (ref "U11") (pin "A8") (pinfunction "VCCQ_A8") (pintype "passive"))
      (node (ref "U11") (pin "B2") (pinfunction "VCC_B2") (pintype "passive"))
      (node (ref "U11") (pin "C1") (pinfunction "VCCQ_C1") (pintype "passive"))
      (node (ref "U11") (pin "C9") (pinfunction "VCCQ_C9") (pintype "passive"))
      (node (ref "U11") (pin "D2") (pinfunction "VCCQ_D2") (pintype "passive"))
      (node (ref "U11") (pin "D9") (pinfunction "VCC_D9") (pintype "passive"))
      (node (ref "U11") (pin "E9") (pinfunction "VCCQ_E9") (pintype "passive"))
      (node (ref "U11") (pin "F1") (pinfunction "VCCQ_F1") (pintype "passive"))
      (node (ref "U11") (pin "G7") (pinfunction "VCC_G7") (pintype "passive"))
      (node (ref "U11") (pin "H2") (pinfunction "VCCQ_H2") (pintype "passive"))
      (node (ref "U11") (pin "H9") (pinfunction "VCCQ_H9") (pintype "passive"))
      (node (ref "U11") (pin "K2") (pinfunction "VCC_K2") (pintype "passive"))
      (node (ref "U11") (pin "K8") (pinfunction "VCC_K8") (pintype "passive"))
      (node (ref "U11") (pin "N1") (pinfunction "VCC_N1") (pintype "passive"))
      (node (ref "U11") (pin "N9") (pinfunction "VCC_N9") (pintype "passive"))
      (node (ref "U11") (pin "R1") (pinfunction "VCC_R1") (pintype "passive"))
      (node (ref "U11") (pin "R9") (pinfunction "VCC_R9") (pintype "passive"))
    )
    (net (code "81") (name "VTT") (class "Default")
      (node (ref "R71") (pin "1") (pinfunction "1_1") (pintype "passive"))
      (node (ref "R72") (pin "1") (pinfunction "1_1") (pintype "passive"))
      (node (ref "R73") (pin "1") (pinfunction "1_1") (pintype "passive"))
      (node (ref "R74") (pin "1") (pinfunction "1_1") (pintype "passive"))
      (node (ref "R75") (pin "1") (pinfunction "1_1") (pintype "passive"))
      (node (ref "R76") (pin "1") (pinfunction "1_1") (pintype "passive"))
      (node (ref "R77") (pin "1") (pinfunction "1_1") (pintype "passive"))
      (node (ref "R78") (pin "1") (pinfunction "1_1") (pintype "passive"))
      (node (ref "R79") (pin "1") (pinfunction "1_1") (pintype "passive"))
      (node (ref "R80") (pin "1") (pinfunction "1_1") (pintype "passive"))
      (node (ref "R81") (pin "1") (pinfunction "1_1") (pintype "passive"))
      (node (ref "R82") (pin "1") (pinfunction "1_1") (pintype "passive"))
      (node (ref "R83") (pin "1") (pinfunction "1_1") (pintype "passive"))
      (node (ref "R84") (pin "1") (pinfunction "1_1") (pintype "passive"))
      (node (ref "R85") (pin "1") (pinfunction "1_1") (pintype "passive"))
      (node (ref "R86") (pin "1") (pinfunction "1_1") (pintype "passive"))
      (node (ref "R87") (pin "1") (pinfunction "1_1") (pintype "passive"))
      (node (ref "R88") (pin "1") (pinfunction "1_1") (pintype "passive"))
      (node (ref "R89") (pin "1") (pinfunction "1_1") (pintype "passive"))
      (node (ref "R90") (pin "1") (pinfunction "1_1") (pintype "passive"))
      (node (ref "R91") (pin "1") (pinfunction "1_1") (pintype "passive"))
      (node (ref "R92") (pin "1") (pinfunction "1_1") (pintype "passive"))
      (node (ref "R93") (pin "1") (pinfunction "1_1") (pintype "passive"))
      (node (ref "R94") (pin "1") (pinfunction "1_1") (pintype "passive"))
    )
    (net (code "82") (name "VTTREF") (class "Default")
      (node (ref "C65") (pin "1") (pinfunction "1_1") (pintype "passive"))
      (node (ref "C66") (pin "1") (pinfunction "1_1") (pintype "passive"))
      (node (ref "U10") (pin "H1") (pinfunction "VREFDQ_H1") (pintype "passive"))
      (node (ref "U10") (pin "M8") (pinfunction "VREFCA_M8") (pintype "passive"))
      (node (ref "U11") (pin "H1") (pinfunction "VREFDQ_H1") (pintype "passive"))
      (node (ref "U11") (pin "M8") (pinfunction "VREFCA_M8") (pintype "passive"))
    )
    (net (code "83") (name "unconnected-(U10-NC(A15)-PadM7)") (class "Default")
      (node (ref "U10") (pin "M7") (pinfunction "NC(A15)_M7") (pintype "passive"))
    )
    (net (code "84") (name "unconnected-(U10-NC-PadJ1)") (class "Default")
      (node (ref "U10") (pin "J1") (pinfunction "NC_J1") (pintype "passive"))
    )
    (net (code "85") (name "unconnected-(U10-NC-PadJ9)") (class "Default")
      (node (ref "U10") (pin "J9") (pinfunction "NC_J9") (pintype "passive"))
    )
    (net (code "86") (name "unconnected-(U10-NC-PadL1)") (class "Default")
      (node (ref "U10") (pin "L1") (pinfunction "NC_L1") (pintype "passive"))
    )
    (net (code "87") (name "unconnected-(U10-NC-PadL9)") (class "Default")
      (node (ref "U10") (pin "L9") (pinfunction "NC_L9") (pintype "passive"))
    )
    (net (code "88") (name "unconnected-(U11-NC(A15)-PadM7)") (class "Default")
      (node (ref "U11") (pin "M7") (pinfunction "NC(A15)_M7") (pintype "passive"))
    )
    (net (code "89") (name "unconnected-(U11-NC-PadJ1)") (class "Default")
      (node (ref "U11") (pin "J1") (pinfunction "NC_J1") (pintype "passive"))
    )
    (net (code "90") (name "unconnected-(U11-NC-PadJ9)") (class "Default")
      (node (ref "U11") (pin "J9") (pinfunction "NC_J9") (pintype "passive"))
    )
    (net (code "91") (name "unconnected-(U11-NC-PadL1)") (class "Default")
      (node (ref "U11") (pin "L1") (pinfunction "NC_L1") (pintype "passive"))
    )
    (net (code "92") (name "unconnected-(U11-NC-PadL9)") (class "Default")
      (node (ref "U11") (pin "L9") (pinfunction "NC_L9") (pintype "passive"))
    )
  )
)
